# Power_Manengement.net
KiCad netlist of a schematic drawn in Altium Designer
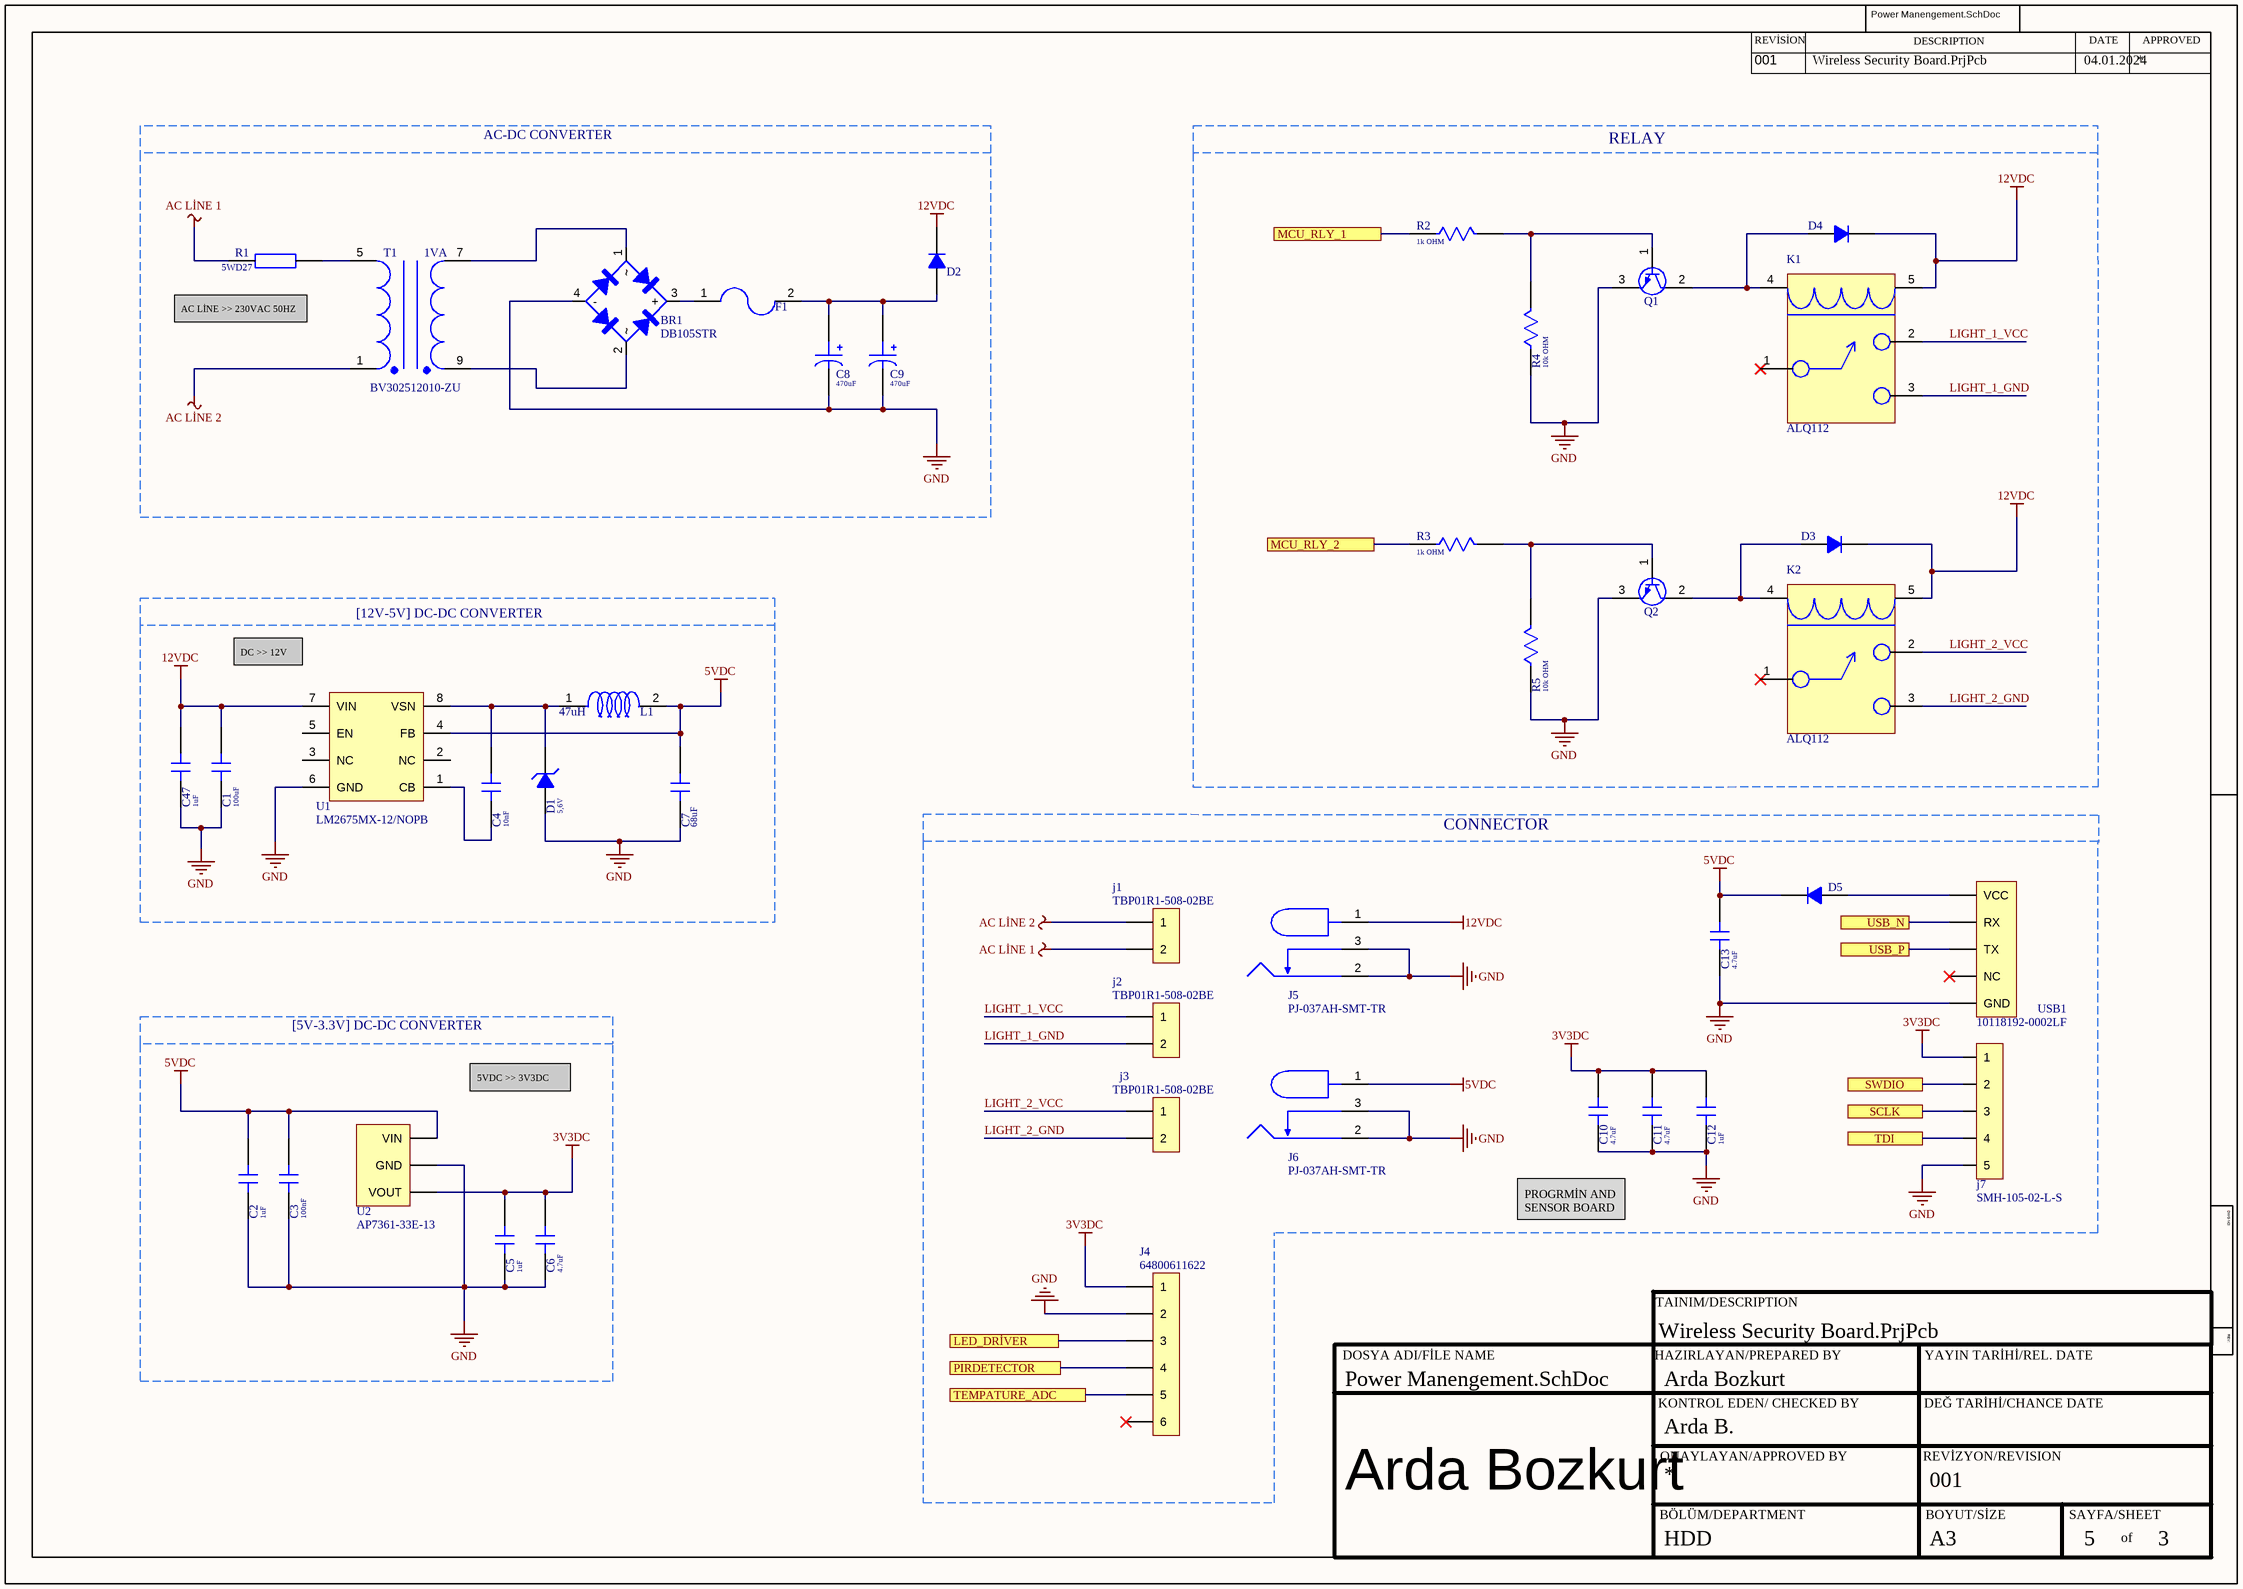
[diagram p0: Power Manengement.SchDoc]

(export (version "E")
  (design (tool "Eeschema 10.0.6"))
  (components
    (comp (ref "BR1")
      (value "DB105STR")
      (footprint "DB105STR")
      (description "Bridge Rect 1PHASE 600V 1A Db-s")
      (fields
        (field (name "MANUFACTURER") "Sangdest Microelectronics")
        (field (name "MANUFACTURER PART NUMBER") "DB105S")
        (field (name "DESIGNED BY") "Arda B.")
      )
      (libsource (lib "FİRST.PROJECT.LİBRARY.~(1)") (part "DB105STR"))
    )
    (comp (ref "C1")
      (value "100uF")
      (footprint "CAP-0805")
      (description "Cap 100UF 4VDC X5R 20% SMD 0805 Embossed Tape")
      (fields
        (field (name "MANUFACTURER") "Murata")
        (field (name "MANUFACTURER PART NUMBER") "GRM21BR60G107ME11K")
        (field (name "DESIGNED BY") "Arda B.")
      )
      (libsource (lib "FİRST.PROJECT.LİBRARY.~(1)") (part "CAP CER 100uF 0805"))
    )
    (comp (ref "C2")
      (value "1uF")
      (footprint "CAP-0805")
      (description "Multilayer Ceramic Capacitor, 1 uF, 25 V, ± 10%, X7R, 0805 [2012 Metric]")
      (fields
        (field (name "MANUFACTURER") "Samsung")
        (field (name "MANUFACTURER PART NUMBER") "CL21B105KAFNNNE")
        (field (name "DESIGNED BY") "Arda B.")
      )
      (libsource (lib "FİRST.PROJECT.LİBRARY.~(1)") (part "CAP CER 1uF 0805"))
    )
    (comp (ref "C3")
      (value "100nF")
      (footprint "CAP-0603")
      (description "Capacitor, 0.1UF, 100V, MLCC, 0603;")
      (fields
        (field (name "MANUFACTURER") "KEMET")
        (field (name "MANUFACTURER PART NUMBER") "C0603C104K1RACTU")
        (field (name "DESIGNED BY") "Arda B.")
      )
      (libsource (lib "FİRST.PROJECT.LİBRARY.~(1)") (part "CAP CER 100nF 0603"))
    )
    (comp (ref "C4")
      (value "10nF")
      (footprint "CAP-0603")
      (description "0603 16V X7R .01uF 10% multilayer ceramic capacitor")
      (fields
        (field (name "MANUFACTURER") "Walsin Technologies")
        (field (name "MANUFACTURER PART NUMBER") "0603B103K160CT")
        (field (name "DESIGNED BY") "Arda B.")
      )
      (libsource (lib "FİRST.PROJECT.LİBRARY.~(1)") (part "CAP CER 10nF 0603"))
    )
    (comp (ref "C5")
      (value "1uF")
      (footprint "CAP-0805")
      (description "Multilayer Ceramic Capacitor, 1 uF, 25 V, ± 10%, X7R, 0805 [2012 Metric]")
      (fields
        (field (name "MANUFACTURER") "Samsung")
        (field (name "MANUFACTURER PART NUMBER") "CL21B105KAFNNNE")
        (field (name "DESIGNED BY") "Arda B.")
      )
      (libsource (lib "FİRST.PROJECT.LİBRARY.~(1)") (part "CAP CER 1uF 0805"))
    )
    (comp (ref "C6")
      (value "4.7uF")
      (footprint "CAP-0805")
      (description "Multilayer Ceramic Capacitor, 4.7 uF, 25 V, ± 10%, X5R, 0805 [2012 Metric]")
      (fields
        (field (name "MANUFACTURER") "Samsung")
        (field (name "MANUFACTURER PART NUMBER") "CL21A475KAQNNNE")
        (field (name "DESIGNED BY") "Arda B.")
      )
      (libsource (lib "FİRST.PROJECT.LİBRARY.~(1)") (part "CAP CER 4.7uF 0805"))
    )
    (comp (ref "C7")
      (value "68uF")
      (footprint "CAP ALUM HYB 68UF 20% 35V SMD")
      (description "Cap Aluminum Lytic 68uF 35V 20%( 6.3 X 7.7mm) SMD 0.34 Ohm 280mA 2000h 105C T/R")
      (fields
        (field (name "MANUFACTURER") "KEMET")
        (field (name "MANUFACTURER PART NUMBER") "EEV686M035A9HAA")
        (field (name "DESIGNED BY") "Arda B.")
      )
      (libsource (lib "FİRST.PROJECT.LİBRARY.~(1)") (part "CAP ALUM 68UF"))
    )
    (comp (ref "C8")
      (value "470uF")
      (footprint "CAP_RADİAL_D1_PS")
      (description "Cap, 470UF, 50V, Alu Elec, Radial")
      (fields
        (field (name "MANUFACTURER") "KEMET")
        (field (name "MANUFACTURER PART NUMBER") "ESH477M050AH4AA")
      )
      (libsource (lib "FİRST.PROJECT.LİBRARY.~(1)") (part "CAP ALUM  POL 470UF"))
    )
    (comp (ref "C9")
      (value "470uF")
      (footprint "CAP_RADİAL_D1_PS")
      (description "Cap, 470UF, 50V, Alu Elec, Radial")
      (fields
        (field (name "MANUFACTURER") "KEMET")
        (field (name "MANUFACTURER PART NUMBER") "ESH477M050AH4AA")
      )
      (libsource (lib "FİRST.PROJECT.LİBRARY.~(1)") (part "CAP ALUM  POL 470UF"))
    )
    (comp (ref "C10")
      (value "4.7uF")
      (footprint "CAP-0805")
      (description "Multilayer Ceramic Capacitor, 4.7 uF, 25 V, ± 10%, X5R, 0805 [2012 Metric]")
      (fields
        (field (name "MANUFACTURER") "Samsung")
        (field (name "MANUFACTURER PART NUMBER") "CL21A475KAQNNNE")
        (field (name "DESIGNED BY") "Arda B.")
      )
      (libsource (lib "FİRST.PROJECT.LİBRARY.~(1)") (part "CAP CER 4.7uF 0805"))
    )
    (comp (ref "C11")
      (value "4.7uF")
      (footprint "CAP-0805")
      (description "Multilayer Ceramic Capacitor, 4.7 uF, 25 V, ± 10%, X5R, 0805 [2012 Metric]")
      (fields
        (field (name "MANUFACTURER") "Samsung")
        (field (name "MANUFACTURER PART NUMBER") "CL21A475KAQNNNE")
        (field (name "DESIGNED BY") "Arda B.")
      )
      (libsource (lib "FİRST.PROJECT.LİBRARY.~(1)") (part "CAP CER 4.7uF 0805"))
    )
    (comp (ref "C12")
      (value "1uF")
      (footprint "CAP-0805")
      (description "Multilayer Ceramic Capacitor, 1 uF, 25 V, ± 10%, X7R, 0805 [2012 Metric]")
      (fields
        (field (name "MANUFACTURER") "Samsung")
        (field (name "MANUFACTURER PART NUMBER") "CL21B105KAFNNNE")
        (field (name "DESIGNED BY") "Arda B.")
      )
      (libsource (lib "FİRST.PROJECT.LİBRARY.~(1)") (part "CAP CER 1uF 0805"))
    )
    (comp (ref "C13")
      (value "4.7uF")
      (footprint "CAP-0805")
      (description "Multilayer Ceramic Capacitor, 4.7 uF, 25 V, ± 10%, X5R, 0805 [2012 Metric]")
      (fields
        (field (name "MANUFACTURER") "Samsung")
        (field (name "MANUFACTURER PART NUMBER") "CL21A475KAQNNNE")
        (field (name "DESIGNED BY") "Arda B.")
      )
      (libsource (lib "FİRST.PROJECT.LİBRARY.~(1)") (part "CAP CER 4.7uF 0805"))
    )
    (comp (ref "C47")
      (value "1uF")
      (footprint "CAP-0805")
      (description "Multilayer Ceramic Capacitor, 1 uF, 25 V, ± 10%, X7R, 0805 [2012 Metric]")
      (fields
        (field (name "MANUFACTURER") "Samsung")
        (field (name "MANUFACTURER PART NUMBER") "CL21B105KAFNNNE")
        (field (name "DESIGNED BY") "Arda B.")
      )
      (libsource (lib "FİRST.PROJECT.LİBRARY.~(1)") (part "CAP CER 1uF 0805"))
    )
    (comp (ref "D1")
      (value "1SMB5919BT3G")
      (footprint "DİODE403A-03")
      (description "Vz=5.6V 5.32V~5.88V Izt=66.9mA")
      (fields
        (field (name "MANUFACTURER") "ON Semiconductor")
        (field (name "WORKIN VOLTAGE") "5,6V")
        (field (name "DESIGNED BY") "Arda B.")
      )
      (libsource (lib "FİRST.PROJECT.LİBRARY.~(1)") (part "1SMB5919BT3G"))
    )
    (comp (ref "D2")
      (value "1N4148WS")
      (footprint "SOT-323")
      (description "Diode Ultra Fast Recovery Rectifier 75V 0.15A 2-Pin SOD-323F T/R")
      (fields
        (field (name "MANUFACTURER") "ON Semiconductor / Fairchild")
        (field (name "DESIGNED BY") "Arda B.")
      )
      (libsource (lib "FİRST.PROJECT.LİBRARY.~(1)") (part "DIODE  75V 150MA SOD323F"))
    )
    (comp (ref "D3")
      (value "1N4148WS")
      (footprint "SOT-323")
      (description "Diode Ultra Fast Recovery Rectifier 75V 0.15A 2-Pin SOD-323F T/R")
      (fields
        (field (name "MANUFACTURER") "ON Semiconductor / Fairchild")
        (field (name "DESIGNED BY") "Arda B.")
      )
      (libsource (lib "FİRST.PROJECT.LİBRARY.~(1)") (part "DIODE  75V 150MA SOD323F"))
    )
    (comp (ref "D4")
      (value "1N4148WS")
      (footprint "SOT-323")
      (description "Diode Ultra Fast Recovery Rectifier 75V 0.15A 2-Pin SOD-323F T/R")
      (fields
        (field (name "MANUFACTURER") "ON Semiconductor / Fairchild")
        (field (name "DESIGNED BY") "Arda B.")
      )
      (libsource (lib "FİRST.PROJECT.LİBRARY.~(1)") (part "DIODE  75V 150MA SOD323F"))
    )
    (comp (ref "D5")
      (value "1N4148WS")
      (footprint "SOT-323")
      (description "Diode Ultra Fast Recovery Rectifier 75V 0.15A 2-Pin SOD-323F T/R")
      (fields
        (field (name "MANUFACTURER") "ON Semiconductor / Fairchild")
        (field (name "DESIGNED BY") "Arda B.")
      )
      (libsource (lib "FİRST.PROJECT.LİBRARY.~(1)") (part "DIODE  75V 150MA SOD323F"))
    )
    (comp (ref "F1")
      (value "3413.0216.22")
      (footprint "FUSE-1206")
      (description "Fuse Chip Fast Acting 1A 32V SMD Solder Pad 1206 Glass T/R VDE/cULus")
      (fields (field (name "MANUFACTURER") "Schurter") (field (name "DESIGNED BY") "Arda B."))
      (libsource (lib "FİRST.PROJECT.LİBRARY.~(1)") (part "FUSE 3413.0216.22"))
    )
    (comp (ref "j1")
      (value "TBP01R1-508-02BE")
      (footprint "TBP01R1-508-02BE")
      (description "2~24 Poles, Pluggable, Receptacle, Horizontal, 5.08 Pitch, Terminal Block Connector")
      (fields (field (name "MANUFACTURER") "CUI Devices") (field (name "DESIGNED BY") "Arda B."))
      (libsource (lib "FİRST.PROJECT.LİBRARY.~(1)") (part "TERMINAL BLOCK, PLUGGABLE, 5.08,"))
    )
    (comp (ref "j2")
      (value "TBP01R1-508-02BE")
      (footprint "TBP01R1-508-02BE")
      (description "2~24 Poles, Pluggable, Receptacle, Horizontal, 5.08 Pitch, Terminal Block Connector")
      (fields (field (name "MANUFACTURER") "CUI Devices") (field (name "DESIGNED BY") "Arda B."))
      (libsource (lib "FİRST.PROJECT.LİBRARY.~(1)") (part "TERMINAL BLOCK, PLUGGABLE, 5.08,"))
    )
    (comp (ref "j3")
      (value "TBP01R1-508-02BE")
      (footprint "TBP01R1-508-02BE")
      (description "2~24 Poles, Pluggable, Receptacle, Horizontal, 5.08 Pitch, Terminal Block Connector")
      (fields (field (name "MANUFACTURER") "CUI Devices") (field (name "DESIGNED BY") "Arda B."))
      (libsource (lib "FİRST.PROJECT.LİBRARY.~(1)") (part "TERMINAL BLOCK, PLUGGABLE, 5.08,"))
    )
    (comp (ref "J4")
      (value "64800611622")
      (footprint "PİN_HEADER_1X6")
      (description "WR-WTB Wire-to-Board Connectors 1.50 mm")
      (fields (field (name "MANUFACTURER") "Wurth Electronics") (field (name "DESIGNED BY.") "Arda B."))
      (libsource (lib "FİRST.PROJECT.LİBRARY.~(1)") (part "PİN HEADER 1X6"))
    )
    (comp (ref "J5")
      (value "PJ-037AH-SMT-TR")
      (footprint "JACK")
      (description "2.0 x 6.3 mm, 5.0 A, Horizontal, Surface Mount (SMT), Dc Power Jack Connector")
      (fields (field (name "MANUFACTURER") "CUI") (field (name "DESIGNED BY") "Arda B."))
      (libsource (lib "FİRST.PROJECT.LİBRARY.~(1)") (part "CONN PWR JACK 2X5.5MM"))
    )
    (comp (ref "J6")
      (value "PJ-037AH-SMT-TR")
      (footprint "JACK")
      (description "2.0 x 6.3 mm, 5.0 A, Horizontal, Surface Mount (SMT), Dc Power Jack Connector")
      (fields (field (name "MANUFACTURER") "CUI") (field (name "DESIGNED BY") "Arda B."))
      (libsource (lib "FİRST.PROJECT.LİBRARY.~(1)") (part "CONN PWR JACK 2X5.5MM"))
    )
    (comp (ref "j7")
      (value "SMH-105-02-L-S")
      (footprint "PİN HEADER 1X5 RA")
      (description "Samtec - SMH-105-02-L-S - Receptacle, 2.54MM, Tht, R/a, 5WAY")
      (fields (field (name "MANUFACTURER") "Samtec") (field (name "DESIGNED BY") "Arda B."))
      (libsource (lib "FİRST.PROJECT.LİBRARY.~(1)") (part "SMH-105-02-L-S"))
    )
    (comp (ref "K1")
      (value "ALQ112")
      (footprint "ALQ112")
      (description "Electromechanical Relay 12VDC 360Ohm 10(NO)/3(NC)A SPDT (( 20mm 10mm 16mm)) THT Power Relay")
      (fields (field (name "MANUFACTURER") "Panasonic") (field (name "DESIGNED BY") "Arda B."))
      (libsource (lib "FİRST.PROJECT.LİBRARY.~(1)") (part "ALQ112"))
    )
    (comp (ref "K2")
      (value "ALQ112")
      (footprint "ALQ112")
      (description "Electromechanical Relay 12VDC 360Ohm 10(NO)/3(NC)A SPDT (( 20mm 10mm 16mm)) THT Power Relay")
      (fields (field (name "MANUFACTURER") "Panasonic") (field (name "DESIGNED BY") "Arda B."))
      (libsource (lib "FİRST.PROJECT.LİBRARY.~(1)") (part "ALQ112"))
    )
    (comp (ref "L1")
      (value "47uH")
      (footprint "IND 1212")
      (description "Power Inductor, Aec-Q200, 47Uh, 0.39A Rohs Compliant: Yes ¦Wurth Elektronik 78438335470")
      (fields
        (field (name "MANUFACTURER") "Wurth Electronics")
        (field (name "MANUFACTURER PART NUMBER") "78438335470")
        (field (name "DESIGNED BY") "Arda B.")
      )
      (libsource (lib "FİRST.PROJECT.LİBRARY.~(1)") (part "IND 47UH 390MA 2.3 OHM SMD"))
    )
    (comp (ref "Q1")
      (value "MMBT3904-7-F")
      (footprint "SOT23-3")
      (description "Transistor General Purpose BJT NPN 40 Volt 0.2A Automotive 3-Pin SOT-23")
      (fields (field (name "MANUFACTURER") "Diodes Zetex") (field (name "DESIGNED BY") "Arda B."))
      (libsource (lib "FİRST.PROJECT.LİBRARY.~(1)") (part "MMBT3904-7-F"))
    )
    (comp (ref "Q2")
      (value "MMBT3904-7-F")
      (footprint "SOT23-3")
      (description "Transistor General Purpose BJT NPN 40 Volt 0.2A Automotive 3-Pin SOT-23")
      (fields (field (name "MANUFACTURER") "Diodes Zetex") (field (name "DESIGNED BY") "Arda B."))
      (libsource (lib "FİRST.PROJECT.LİBRARY.~(1)") (part "MMBT3904-7-F"))
    )
    (comp (ref "R1")
      (value "5WD27")
      (footprint "5WD27")
      (description "RES 0.27 OHM 5% 5W AXIAL")
      (fields
        (field (name "MANUFACTURER") "Multicomp")
        (field (name "MANUFACTURER PART NUMBER") "MP006029")
        (field (name "DESIGNED BY") "Arda B.")
      )
      (libsource (lib "FİRST.PROJECT.LİBRARY.~(1)") (part "5WD27"))
    )
    (comp (ref "R2")
      (value "1k OHM")
      (footprint "RES-0603")
      (description "Res Thick Film 0603 1K Ohm 1% 0.1W(1/10W) ±100ppm/C Pad SMD Automotive T/R")
      (fields
        (field (name "MANUFACTURER") "Stackpole Electronics")
        (field (name "MANUFACTURER PART NUMBER") "RMCF0603FT1K00")
        (field (name "DESIGNED BY") "Arda B.")
      )
      (libsource (lib "FİRST.PROJECT.LİBRARY.~(1)") (part "RES 1K OHM 0603"))
    )
    (comp (ref "R3")
      (value "1k OHM")
      (footprint "RES-0603")
      (description "Res Thick Film 0603 1K Ohm 1% 0.1W(1/10W) ±100ppm/C Pad SMD Automotive T/R")
      (fields
        (field (name "MANUFACTURER") "Stackpole Electronics")
        (field (name "MANUFACTURER PART NUMBER") "RMCF0603FT1K00")
        (field (name "DESIGNED BY") "Arda B.")
      )
      (libsource (lib "FİRST.PROJECT.LİBRARY.~(1)") (part "RES 1K OHM 0603"))
    )
    (comp (ref "R4")
      (value "10k OHM")
      (footprint "RES-0603")
      (description "SMD Chip Resistor, 10 kOhm, ± 1%, 100 mW, 0603 [1608 Metric], Thick Film, General Purpose")
      (fields
        (field (name "MANUFACTURER") "Yageo")
        (field (name "MANUFACTURER PART NUMBER") "RC0603FR-0710KL")
        (field (name "DESIGNED BY") "Arda B.")
      )
      (libsource (lib "FİRST.PROJECT.LİBRARY.~(1)") (part "RES 10K OHM 0603"))
    )
    (comp (ref "R5")
      (value "10k OHM")
      (footprint "RES-0603")
      (description "SMD Chip Resistor, 10 kOhm, ± 1%, 100 mW, 0603 [1608 Metric], Thick Film, General Purpose")
      (fields
        (field (name "MANUFACTURER") "Yageo")
        (field (name "MANUFACTURER PART NUMBER") "RC0603FR-0710KL")
        (field (name "DESIGNED BY") "Arda B.")
      )
      (libsource (lib "FİRST.PROJECT.LİBRARY.~(1)") (part "RES 10K OHM 0603"))
    )
    (comp (ref "T1")
      (value "BV302512010-ZU")
      (footprint "BV302512010-ZU")
      (description "PWR XFMR LAMINATED 1VA TH")
      (fields
        (field (name "MANUFACTURER") "Zettler Magnetics")
        (field (name "RATED POWER") "1VA")
        (field (name "DESIGNED BY") "Arda B.")
      )
      (libsource (lib "FİRST.PROJECT.LİBRARY.~(1)") (part "BV302512010-ZU"))
    )
    (comp (ref "U1")
      (value "LM2675MX-12/NOPB")
      (footprint "SOIC-8")
      (description "SIMPLE SWITCHER® 6.5V to 40V, 1A Low Component Count Step-Down Regulator 8-SOIC -40 to 125")
      (fields
        (field (name "MANUFACTURER") "TI National Semiconductor")
        (field (name "DESIGNED BY") "Arda B.")
      )
      (libsource (lib "FİRST.PROJECT.LİBRARY.~(1)") (part "LM2675MX-12/NOPB"))
    )
    (comp (ref "U2")
      (value "AP7361-33E-13")
      (footprint "SOT223")
      (description "AP7361 Series 3.3 V 1 A Low SMT Dropout Fixed-Mode Regulator - SOT-223")
      (fields (field (name "MANUFACTURER") "Diodes"))
      (libsource (lib "FİRST.PROJECT.LİBRARY.~(1)") (part "AP7361-33E-13"))
    )
    (comp (ref "USB1")
      (value "10118192-0002LF")
      (footprint "MİCRO_B_USB")
      (description "2.50mm Pitch, Mini-Lock Receptacle Crimp Housing, Single Row, Positive Lock, 2 Circuits, Natural")
      (fields
        (field (name "MANUFACTURER") "Molex")
        (field (name "MANUFACTURER PART NUMBER") "51103-0200")
        (field (name "DESIGNED BY") "Arda B.")
      )
      (libsource (lib "FİRST.PROJECT.LİBRARY.~(1)") (part "MİCRO B USB CONN"))
    )
  )
  (nets
    (net (code "1") (name "/LED_DRİVER") (class "Default")
      (node (ref "J4") (pin "3") (pinfunction "3_3") (pintype "power_in"))
    )
    (net (code "2") (name "/LIGHT_1_GND") (class "Default")
      (node (ref "K1") (pin "3") (pinfunction "3_3") (pintype "passive"))
      (node (ref "j2") (pin "2") (pinfunction "2_2") (pintype "passive"))
    )
    (net (code "3") (name "/LIGHT_1_VCC") (class "Default")
      (node (ref "K1") (pin "2") (pinfunction "2_2") (pintype "passive"))
      (node (ref "j2") (pin "1") (pinfunction "1_1") (pintype "passive"))
    )
    (net (code "4") (name "/LIGHT_2_GND") (class "Default")
      (node (ref "K2") (pin "3") (pinfunction "3_3") (pintype "passive"))
      (node (ref "j3") (pin "2") (pinfunction "2_2") (pintype "passive"))
    )
    (net (code "5") (name "/LIGHT_2_VCC") (class "Default")
      (node (ref "K2") (pin "2") (pinfunction "2_2") (pintype "passive"))
      (node (ref "j3") (pin "1") (pinfunction "1_1") (pintype "passive"))
    )
    (net (code "6") (name "/MCU_RLY_1") (class "Default")
      (node (ref "R2") (pin "1") (pinfunction "1_1") (pintype "passive"))
    )
    (net (code "7") (name "/MCU_RLY_2") (class "Default")
      (node (ref "R3") (pin "1") (pinfunction "1_1") (pintype "passive"))
    )
    (net (code "8") (name "/PIRDETECTOR") (class "Default")
      (node (ref "J4") (pin "4") (pinfunction "4_4") (pintype "power_in"))
    )
    (net (code "9") (name "/SCLK") (class "Default")
      (node (ref "j7") (pin "3") (pinfunction "3_3") (pintype "passive"))
    )
    (net (code "10") (name "/SWDIO") (class "Default")
      (node (ref "j7") (pin "2") (pinfunction "2_2") (pintype "passive"))
    )
    (net (code "11") (name "/TDI") (class "Default")
      (node (ref "j7") (pin "4") (pinfunction "4_4") (pintype "passive"))
    )
    (net (code "12") (name "/TEMPATURE_ADC") (class "Default")
      (node (ref "J4") (pin "5") (pinfunction "5_5") (pintype "power_in"))
    )
    (net (code "13") (name "/USB_N") (class "Default")
      (node (ref "USB1") (pin "2") (pinfunction "RX_2") (pintype "power_in"))
    )
    (net (code "14") (name "/USB_P") (class "Default")
      (node (ref "USB1") (pin "3") (pinfunction "TX_3") (pintype "power_in"))
    )
    (net (code "15") (name "3V3DC") (class "Default")
      (node (ref "C10") (pin "2") (pinfunction "2_2") (pintype "passive"))
      (node (ref "C11") (pin "2") (pinfunction "2_2") (pintype "passive"))
      (node (ref "C12") (pin "2") (pinfunction "2_2") (pintype "passive"))
      (node (ref "C5") (pin "2") (pinfunction "2_2") (pintype "passive"))
      (node (ref "C6") (pin "2") (pinfunction "2_2") (pintype "passive"))
      (node (ref "J4") (pin "1") (pinfunction "1_1") (pintype "power_in"))
      (node (ref "U2") (pin "3") (pinfunction "VOUT_3") (pintype "passive"))
      (node (ref "j7") (pin "1") (pinfunction "1_1") (pintype "passive"))
    )
    (net (code "16") (name "5VDC") (class "Default")
      (node (ref "C13") (pin "2") (pinfunction "2_2") (pintype "passive"))
      (node (ref "C2") (pin "2") (pinfunction "2_2") (pintype "passive"))
      (node (ref "C3") (pin "2") (pinfunction "2_2") (pintype "passive"))
      (node (ref "C7") (pin "2") (pinfunction "2_2") (pintype "passive"))
      (node (ref "D5") (pin "1") (pinfunction "1_1") (pintype "passive"))
      (node (ref "J6") (pin "1") (pinfunction "VCC_1") (pintype "passive"))
      (node (ref "L1") (pin "2") (pinfunction "2_2") (pintype "passive"))
      (node (ref "U1") (pin "4") (pinfunction "FB_4") (pintype "passive"))
      (node (ref "U2") (pin "1") (pinfunction "VIN_1") (pintype "passive"))
    )
    (net (code "17") (name "12VDC") (class "Default")
      (node (ref "C1") (pin "2") (pinfunction "2_2") (pintype "passive"))
      (node (ref "C47") (pin "2") (pinfunction "2_2") (pintype "passive"))
      (node (ref "D2") (pin "1") (pinfunction "1_1") (pintype "passive"))
      (node (ref "D3") (pin "1") (pinfunction "1_1") (pintype "passive"))
      (node (ref "D4") (pin "1") (pinfunction "1_1") (pintype "passive"))
      (node (ref "J5") (pin "1") (pinfunction "VCC_1") (pintype "passive"))
      (node (ref "K1") (pin "5") (pinfunction "5_5") (pintype "passive"))
      (node (ref "K2") (pin "5") (pinfunction "5_5") (pintype "passive"))
      (node (ref "U1") (pin "7") (pinfunction "VIN_7") (pintype "passive"))
    )
    (net (code "18") (name "AC LİNE 1") (class "Default")
      (node (ref "R1") (pin "1") (pinfunction "1_1") (pintype "passive"))
      (node (ref "j1") (pin "2") (pinfunction "2_2") (pintype "passive"))
    )
    (net (code "19") (name "AC LİNE 2") (class "Default")
      (node (ref "T1") (pin "1") (pinfunction "1_1") (pintype "passive"))
      (node (ref "j1") (pin "1") (pinfunction "1_1") (pintype "passive"))
    )
    (net (code "20") (name "GND") (class "Default")
      (node (ref "BR1") (pin "4") (pinfunction "-_4") (pintype "passive"))
      (node (ref "C1") (pin "1") (pinfunction "1_1") (pintype "passive"))
      (node (ref "C10") (pin "1") (pinfunction "1_1") (pintype "passive"))
      (node (ref "C11") (pin "1") (pinfunction "1_1") (pintype "passive"))
      (node (ref "C12") (pin "1") (pinfunction "1_1") (pintype "passive"))
      (node (ref "C13") (pin "1") (pinfunction "1_1") (pintype "passive"))
      (node (ref "C2") (pin "1") (pinfunction "1_1") (pintype "passive"))
      (node (ref "C3") (pin "1") (pinfunction "1_1") (pintype "passive"))
      (node (ref "C47") (pin "1") (pinfunction "1_1") (pintype "passive"))
      (node (ref "C5") (pin "1") (pinfunction "1_1") (pintype "passive"))
      (node (ref "C6") (pin "1") (pinfunction "1_1") (pintype "passive"))
      (node (ref "C7") (pin "1") (pinfunction "1_1") (pintype "passive"))
      (node (ref "C8") (pin "2") (pinfunction "2_2") (pintype "passive"))
      (node (ref "C9") (pin "2") (pinfunction "2_2") (pintype "passive"))
      (node (ref "D1") (pin "1") (pinfunction "1_1") (pintype "passive"))
      (node (ref "J4") (pin "2") (pinfunction "2_2") (pintype "power_in"))
      (node (ref "J5") (pin "2") (pinfunction "GND_2") (pintype "passive"))
      (node (ref "J5") (pin "3") (pinfunction "SH_3") (pintype "passive"))
      (node (ref "J6") (pin "2") (pinfunction "GND_2") (pintype "passive"))
      (node (ref "J6") (pin "3") (pinfunction "SH_3") (pintype "passive"))
      (node (ref "Q1") (pin "3") (pinfunction "E_3") (pintype "passive"))
      (node (ref "Q2") (pin "3") (pinfunction "E_3") (pintype "passive"))
      (node (ref "R4") (pin "1") (pinfunction "1_1") (pintype "passive"))
      (node (ref "R5") (pin "1") (pinfunction "1_1") (pintype "passive"))
      (node (ref "U1") (pin "6") (pinfunction "GND_6") (pintype "passive"))
      (node (ref "U2") (pin "2") (pinfunction "GND_2") (pintype "passive"))
      (node (ref "USB1") (pin "5") (pinfunction "GND_5") (pintype "power_in"))
      (node (ref "j7") (pin "5") (pinfunction "5_5") (pintype "passive"))
    )
    (net (code "21") (name "Net-(BR1-+)") (class "Default")
      (node (ref "BR1") (pin "3") (pinfunction "+_3") (pintype "passive"))
      (node (ref "F1") (pin "1") (pinfunction "1_1") (pintype "passive"))
    )
    (net (code "22") (name "Net-(BR1-~-Pad1)") (class "Default")
      (node (ref "BR1") (pin "1") (pinfunction "~_1") (pintype "passive"))
      (node (ref "T1") (pin "7") (pinfunction "7_7") (pintype "passive"))
    )
    (net (code "23") (name "Net-(BR1-~-Pad2)") (class "Default")
      (node (ref "BR1") (pin "2") (pinfunction "~_2") (pintype "passive"))
      (node (ref "T1") (pin "9") (pinfunction "9_9") (pintype "passive"))
    )
    (net (code "24") (name "Net-(C8-Pad1)") (class "Default")
      (node (ref "C8") (pin "1") (pinfunction "1_1") (pintype "passive"))
      (node (ref "C9") (pin "1") (pinfunction "1_1") (pintype "passive"))
      (node (ref "D2") (pin "2") (pinfunction "2_2") (pintype "passive"))
      (node (ref "F1") (pin "2") (pinfunction "2_2") (pintype "passive"))
    )
    (net (code "25") (name "Net-(Q1-B)") (class "Default")
      (node (ref "Q1") (pin "1") (pinfunction "B_1") (pintype "passive"))
      (node (ref "R2") (pin "2") (pinfunction "2_2") (pintype "passive"))
      (node (ref "R4") (pin "2") (pinfunction "2_2") (pintype "passive"))
    )
    (net (code "26") (name "Net-(Q1-C)") (class "Default")
      (node (ref "D4") (pin "2") (pinfunction "2_2") (pintype "passive"))
      (node (ref "K1") (pin "4") (pinfunction "4_4") (pintype "passive"))
      (node (ref "Q1") (pin "2") (pinfunction "C_2") (pintype "passive"))
    )
    (net (code "27") (name "Net-(Q2-B)") (class "Default")
      (node (ref "Q2") (pin "1") (pinfunction "B_1") (pintype "passive"))
      (node (ref "R3") (pin "2") (pinfunction "2_2") (pintype "passive"))
      (node (ref "R5") (pin "2") (pinfunction "2_2") (pintype "passive"))
    )
    (net (code "28") (name "Net-(Q2-C)") (class "Default")
      (node (ref "D3") (pin "2") (pinfunction "2_2") (pintype "passive"))
      (node (ref "K2") (pin "4") (pinfunction "4_4") (pintype "passive"))
      (node (ref "Q2") (pin "2") (pinfunction "C_2") (pintype "passive"))
    )
    (net (code "29") (name "Net-(R1-Pad2)") (class "Default")
      (node (ref "R1") (pin "2") (pinfunction "2_2") (pintype "passive"))
      (node (ref "T1") (pin "5") (pinfunction "5_5") (pintype "passive"))
    )
    (net (code "30") (name "Net-(U1-CB)") (class "Default")
      (node (ref "C4") (pin "2") (pinfunction "2_2") (pintype "passive"))
      (node (ref "U1") (pin "1") (pinfunction "CB_1") (pintype "passive"))
    )
    (net (code "31") (name "Net-(U1-VSN)") (class "Default")
      (node (ref "C4") (pin "1") (pinfunction "1_1") (pintype "passive"))
      (node (ref "D1") (pin "2") (pinfunction "2_2") (pintype "passive"))
      (node (ref "L1") (pin "1") (pinfunction "1_1") (pintype "passive"))
      (node (ref "U1") (pin "8") (pinfunction "VSN_8") (pintype "passive"))
    )
    (net (code "32") (name "Net-(USB1-VCC)") (class "Default")
      (node (ref "D5") (pin "2") (pinfunction "2_2") (pintype "passive"))
      (node (ref "USB1") (pin "1") (pinfunction "VCC_1") (pintype "power_in"))
    )
    (net (code "33") (name "unconnected-(J4-Pad6)") (class "Default")
      (node (ref "J4") (pin "6") (pinfunction "6_6") (pintype "power_in+no_connect"))
    )
    (net (code "34") (name "unconnected-(K1-Pad1)") (class "Default")
      (node (ref "K1") (pin "1") (pinfunction "1_1") (pintype "passive+no_connect"))
    )
    (net (code "35") (name "unconnected-(K2-Pad1)") (class "Default")
      (node (ref "K2") (pin "1") (pinfunction "1_1") (pintype "passive+no_connect"))
    )
    (net (code "36") (name "unconnected-(U1-EN-Pad5)") (class "Default")
      (node (ref "U1") (pin "5") (pinfunction "EN_5") (pintype "passive"))
    )
    (net (code "37") (name "unconnected-(U1-NC-Pad2)") (class "Default")
      (node (ref "U1") (pin "2") (pinfunction "NC_2") (pintype "passive"))
    )
    (net (code "38") (name "unconnected-(U1-NC-Pad3)") (class "Default")
      (node (ref "U1") (pin "3") (pinfunction "NC_3") (pintype "passive"))
    )
    (net (code "39") (name "unconnected-(USB1-NC-Pad4)") (class "Default")
      (node (ref "USB1") (pin "4") (pinfunction "NC_4") (pintype "power_in+no_connect"))
    )
  )
)
